# measurementBoard.net
KiCad netlist of a schematic drawn in EAGLE
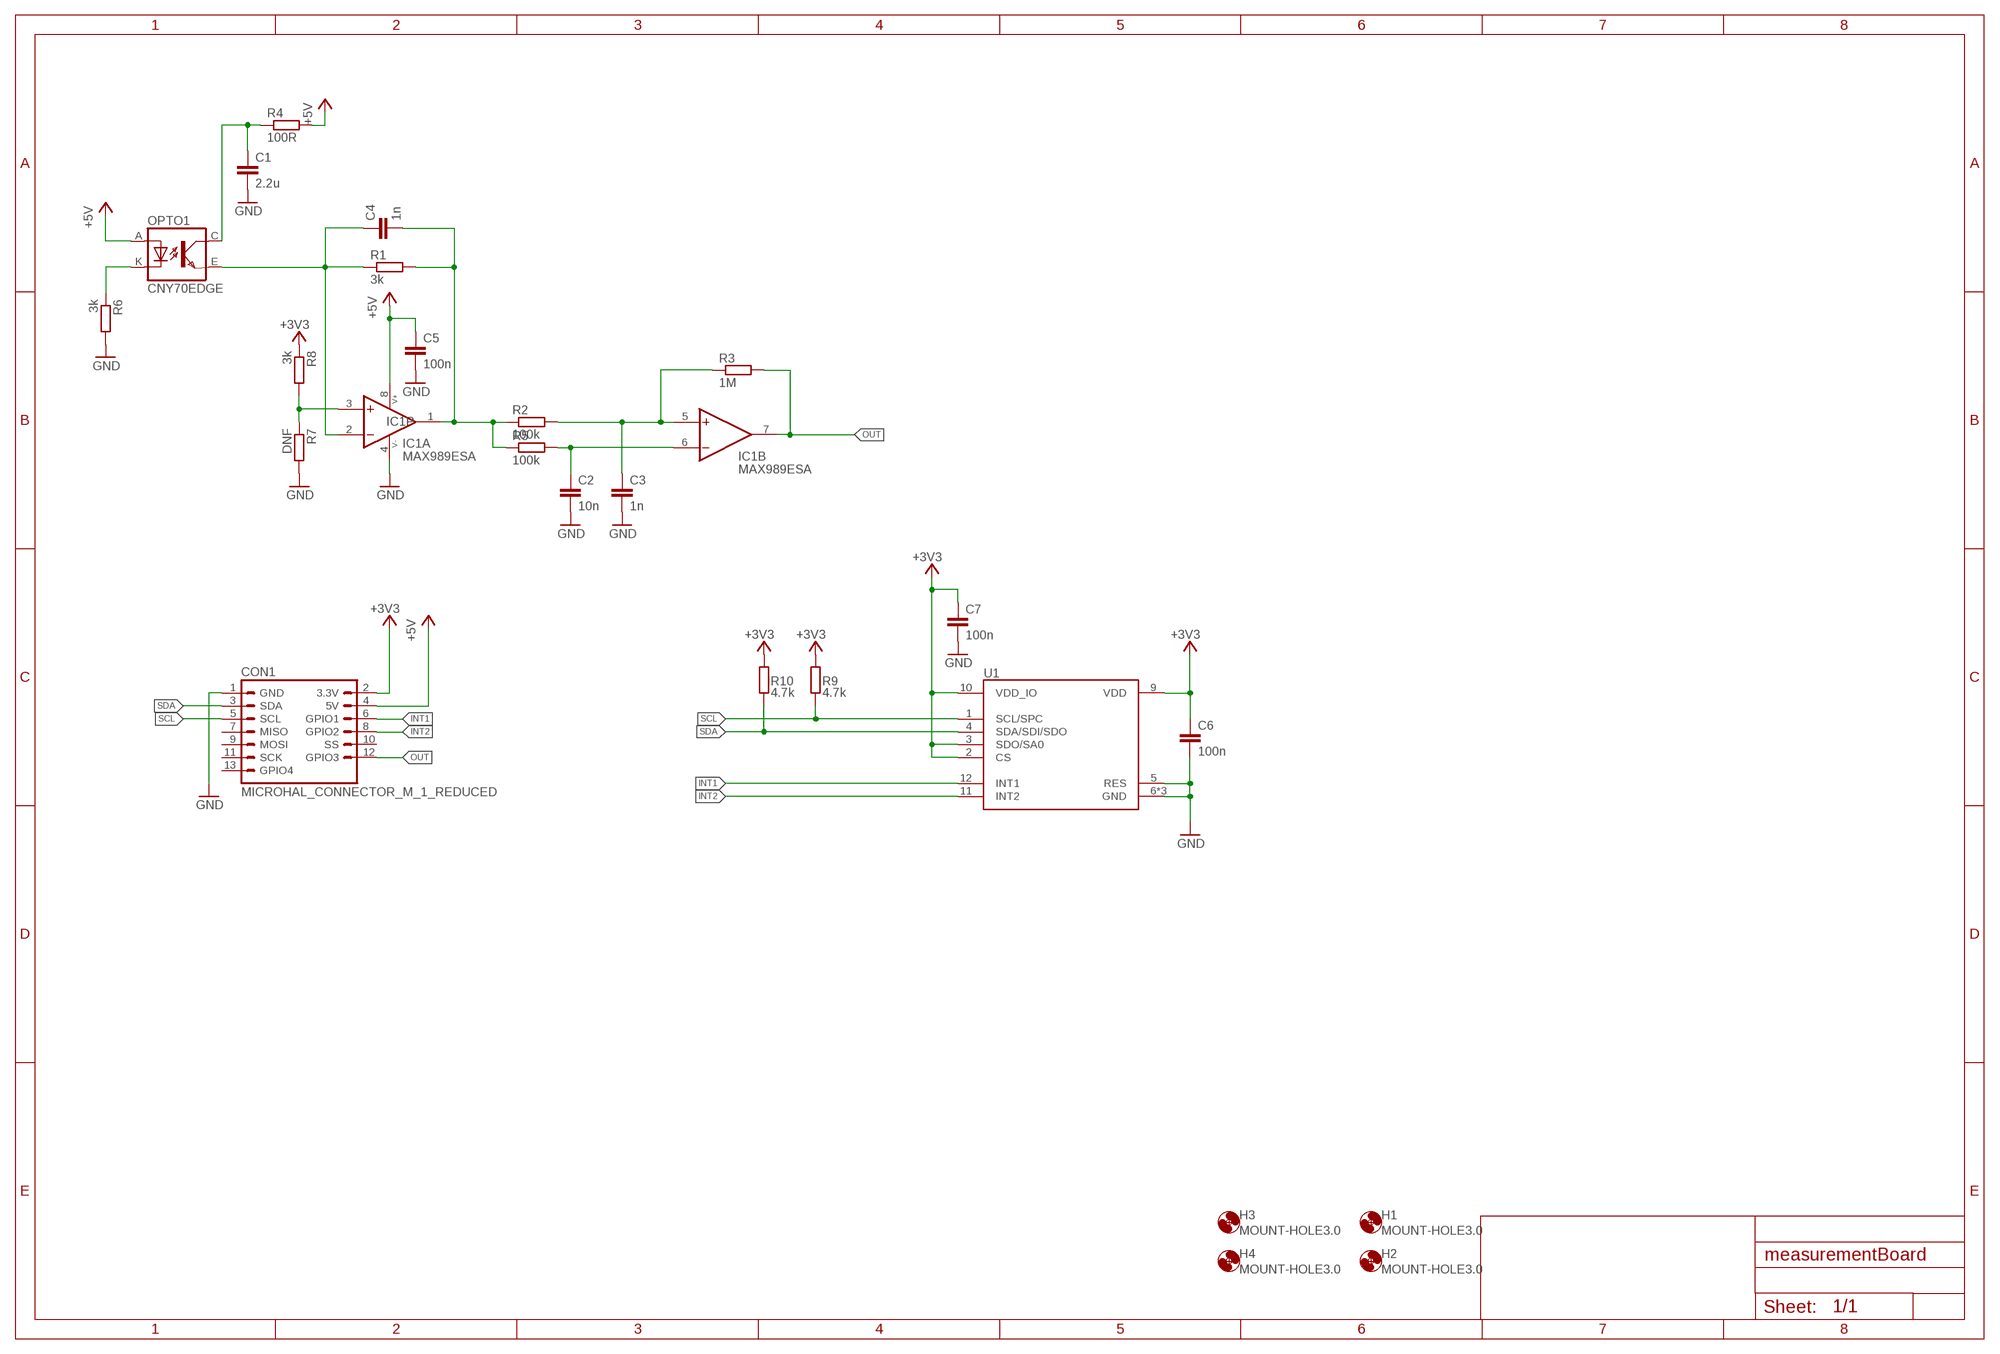
[diagram p0: schematic, sheet 1]

(export (version "E")
  (design (tool "Eeschema 10.0.6"))
  (components
    (comp (ref "C1")
      (value "2.2u")
      (footprint "eagle-import:C0603K")
      (libsource (lib "eagle-import") (part "C-EUC0603K"))
    )
    (comp (ref "C2")
      (value "10n")
      (footprint "eagle-import:C0603K")
      (libsource (lib "eagle-import") (part "C-EUC0603K"))
    )
    (comp (ref "C3")
      (value "1n")
      (footprint "eagle-import:C0603K")
      (libsource (lib "eagle-import") (part "C-EUC0603K"))
    )
    (comp (ref "C4")
      (value "1n")
      (footprint "eagle-import:C0603K")
      (libsource (lib "eagle-import") (part "C-EUC0603K"))
    )
    (comp (ref "C5")
      (value "100n")
      (footprint "eagle-import:C0603K")
      (libsource (lib "eagle-import") (part "C-EUC0603K"))
    )
    (comp (ref "C6")
      (value "100n")
      (footprint "eagle-import:C0603K")
      (libsource (lib "eagle-import") (part "C-EUC0603K"))
    )
    (comp (ref "C7")
      (value "100n")
      (footprint "eagle-import:C0603K")
      (libsource (lib "eagle-import") (part "C-EUC0603K"))
    )
    (comp (ref "CON1")
      (value "MICROHAL_CONNECTOR_M_1_REDUCED")
      (footprint "eagle-import:MICROHAL_CONNECTOR_M_1_REDUCED_EDGE")
      (libsource (lib "eagle-import") (part "MICROHAL_CONNECTOR_M_1_REDUCED"))
    )
    (comp (ref "H1")
      (value "MOUNT-HOLE3.0")
      (footprint "eagle-import:3,0")
      (libsource (lib "eagle-import") (part "MOUNT-HOLE3.0"))
    )
    (comp (ref "H2")
      (value "MOUNT-HOLE3.0")
      (footprint "eagle-import:3,0")
      (libsource (lib "eagle-import") (part "MOUNT-HOLE3.0"))
    )
    (comp (ref "H3")
      (value "MOUNT-HOLE3.0")
      (footprint "eagle-import:3,0")
      (libsource (lib "eagle-import") (part "MOUNT-HOLE3.0"))
    )
    (comp (ref "H4")
      (value "MOUNT-HOLE3.0")
      (footprint "eagle-import:3,0")
      (libsource (lib "eagle-import") (part "MOUNT-HOLE3.0"))
    )
    (comp (ref "IC1")
      (value "MAX989ESA")
      (footprint "eagle-import:SO08")
      (fields (field (name "MF") "MAXIM") (field (name "MPN") "MAX989ESA+"))
      (libsource (lib "eagle-import") (part "MAX9ESA89"))
    )
    (comp (ref "OPTO1")
      (value "CNY70EDGE")
      (footprint "eagle-import:CNY70_EDGE")
      (libsource (lib "eagle-import") (part "CNY70EDGE"))
    )
    (comp (ref "R1")
      (value "3k")
      (footprint "eagle-import:R0603")
      (libsource (lib "eagle-import") (part "R-EU_R0603"))
    )
    (comp (ref "R2")
      (value "100k")
      (footprint "eagle-import:R0603")
      (libsource (lib "eagle-import") (part "R-EU_R0603"))
    )
    (comp (ref "R3")
      (value "1M")
      (footprint "eagle-import:R0603")
      (libsource (lib "eagle-import") (part "R-EU_R0603"))
    )
    (comp (ref "R4")
      (value "100R")
      (footprint "eagle-import:R0603")
      (libsource (lib "eagle-import") (part "R-EU_R0603"))
    )
    (comp (ref "R5")
      (value "100k")
      (footprint "eagle-import:R0603")
      (libsource (lib "eagle-import") (part "R-EU_R0603"))
    )
    (comp (ref "R6")
      (value "3k")
      (footprint "eagle-import:R0603")
      (libsource (lib "eagle-import") (part "R-EU_R0603"))
    )
    (comp (ref "R7")
      (value "DNF")
      (footprint "eagle-import:R0603")
      (libsource (lib "eagle-import") (part "R-EU_R0603"))
    )
    (comp (ref "R8")
      (value "3k")
      (footprint "eagle-import:R0603")
      (libsource (lib "eagle-import") (part "R-EU_R0603"))
    )
    (comp (ref "R9")
      (value "4.7k")
      (footprint "eagle-import:R0603")
      (libsource (lib "eagle-import") (part "R-EU_R0603"))
    )
    (comp (ref "R10")
      (value "4.7k")
      (footprint "eagle-import:R0603")
      (libsource (lib "eagle-import") (part "R-EU_R0603"))
    )
    (comp (ref "U1")
      (value "LIS2DH12")
      (footprint "eagle-import:LGA-12")
      (libsource (lib "eagle-import") (part "LIS2DH12"))
    )
  )
  (nets
    (net (code "1") (name "+3V3") (class "Default")
      (node (ref "C6") (pin "1") (pinfunction "1_1") (pintype "passive"))
      (node (ref "C7") (pin "1") (pinfunction "1_1") (pintype "passive"))
      (node (ref "CON1") (pin "2") (pinfunction "3.3V_2") (pintype "passive"))
      (node (ref "R10") (pin "1") (pinfunction "1_1") (pintype "passive"))
      (node (ref "R8") (pin "1") (pinfunction "1_1") (pintype "passive"))
      (node (ref "R9") (pin "1") (pinfunction "1_1") (pintype "passive"))
      (node (ref "U1") (pin "10") (pinfunction "VDD_IO_10") (pintype "power_in"))
      (node (ref "U1") (pin "2") (pinfunction "CS_2") (pintype "bidirectional"))
      (node (ref "U1") (pin "3") (pinfunction "SDO/SA0_3") (pintype "bidirectional"))
      (node (ref "U1") (pin "9") (pinfunction "VDD_9") (pintype "power_in"))
    )
    (net (code "2") (name "+5V") (class "Default")
      (node (ref "C5") (pin "1") (pinfunction "1_1") (pintype "passive"))
      (node (ref "CON1") (pin "4") (pinfunction "5V_4") (pintype "passive"))
      (node (ref "IC1") (pin "8") (pinfunction "V+_8") (pintype "power_in"))
      (node (ref "OPTO1") (pin "A") (pinfunction "A_A") (pintype "passive"))
      (node (ref "R4") (pin "2") (pinfunction "2_2") (pintype "passive"))
    )
    (net (code "3") (name "GND") (class "Default")
      (node (ref "C1") (pin "2") (pinfunction "2_2") (pintype "passive"))
      (node (ref "C2") (pin "2") (pinfunction "2_2") (pintype "passive"))
      (node (ref "C3") (pin "2") (pinfunction "2_2") (pintype "passive"))
      (node (ref "C5") (pin "2") (pinfunction "2_2") (pintype "passive"))
      (node (ref "C6") (pin "2") (pinfunction "2_2") (pintype "passive"))
      (node (ref "C7") (pin "2") (pinfunction "2_2") (pintype "passive"))
      (node (ref "CON1") (pin "1") (pinfunction "GND_1") (pintype "passive"))
      (node (ref "IC1") (pin "4") (pinfunction "V-_4") (pintype "power_in"))
      (node (ref "R6") (pin "2") (pinfunction "2_2") (pintype "passive"))
      (node (ref "R7") (pin "2") (pinfunction "2_2") (pintype "passive"))
      (node (ref "U1") (pin "5") (pinfunction "RES_5") (pintype "power_in"))
      (node (ref "U1") (pin "6") (pinfunction "GND_6") (pintype "power_in"))
      (node (ref "U1") (pin "7") (pinfunction "GND_7") (pintype "power_in"))
      (node (ref "U1") (pin "8") (pinfunction "GND_8") (pintype "power_in"))
    )
    (net (code "4") (name "INT1") (class "Default")
      (node (ref "CON1") (pin "6") (pinfunction "GPIO1_6") (pintype "passive"))
      (node (ref "U1") (pin "12") (pinfunction "INT1_12") (pintype "output"))
    )
    (net (code "5") (name "INT2") (class "Default")
      (node (ref "CON1") (pin "8") (pinfunction "GPIO2_8") (pintype "passive"))
      (node (ref "U1") (pin "11") (pinfunction "INT2_11") (pintype "output"))
    )
    (net (code "6") (name "Net-(IC1A-+IN)") (class "Default")
      (node (ref "IC1") (pin "3") (pinfunction "+IN_3") (pintype "input"))
      (node (ref "R7") (pin "1") (pinfunction "1_1") (pintype "passive"))
      (node (ref "R8") (pin "2") (pinfunction "2_2") (pintype "passive"))
    )
    (net (code "7") (name "Net-(IC1A--IN)") (class "Default")
      (node (ref "C4") (pin "1") (pinfunction "1_1") (pintype "passive"))
      (node (ref "IC1") (pin "2") (pinfunction "-IN_2") (pintype "input"))
      (node (ref "OPTO1") (pin "E") (pinfunction "EMI_E") (pintype "passive"))
      (node (ref "R1") (pin "1") (pinfunction "1_1") (pintype "passive"))
    )
    (net (code "8") (name "Net-(IC1A-OUT)") (class "Default")
      (node (ref "C4") (pin "2") (pinfunction "2_2") (pintype "passive"))
      (node (ref "IC1") (pin "1") (pinfunction "OUT_1") (pintype "output"))
      (node (ref "R1") (pin "2") (pinfunction "2_2") (pintype "passive"))
      (node (ref "R2") (pin "1") (pinfunction "1_1") (pintype "passive"))
      (node (ref "R5") (pin "1") (pinfunction "1_1") (pintype "passive"))
    )
    (net (code "9") (name "Net-(IC1B-+IN)") (class "Default")
      (node (ref "C3") (pin "1") (pinfunction "1_1") (pintype "passive"))
      (node (ref "IC1") (pin "5") (pinfunction "+IN_5") (pintype "input"))
      (node (ref "R2") (pin "2") (pinfunction "2_2") (pintype "passive"))
      (node (ref "R3") (pin "1") (pinfunction "1_1") (pintype "passive"))
    )
    (net (code "10") (name "Net-(IC1B--IN)") (class "Default")
      (node (ref "C2") (pin "1") (pinfunction "1_1") (pintype "passive"))
      (node (ref "IC1") (pin "6") (pinfunction "-IN_6") (pintype "input"))
      (node (ref "R5") (pin "2") (pinfunction "2_2") (pintype "passive"))
    )
    (net (code "11") (name "Net-(OPTO1-C)") (class "Default")
      (node (ref "OPTO1") (pin "K") (pinfunction "C_K") (pintype "passive"))
      (node (ref "R6") (pin "1") (pinfunction "1_1") (pintype "passive"))
    )
    (net (code "12") (name "Net-(OPTO1-COL)") (class "Default")
      (node (ref "C1") (pin "1") (pinfunction "1_1") (pintype "passive"))
      (node (ref "OPTO1") (pin "C") (pinfunction "COL_C") (pintype "passive"))
      (node (ref "R4") (pin "1") (pinfunction "1_1") (pintype "passive"))
    )
    (net (code "13") (name "OUT") (class "Default")
      (node (ref "CON1") (pin "12") (pinfunction "GPIO3_12") (pintype "bidirectional"))
      (node (ref "IC1") (pin "7") (pinfunction "OUT_7") (pintype "output"))
      (node (ref "R3") (pin "2") (pinfunction "2_2") (pintype "passive"))
    )
    (net (code "14") (name "SCL") (class "Default")
      (node (ref "CON1") (pin "5") (pinfunction "SCL_5") (pintype "passive"))
      (node (ref "R9") (pin "2") (pinfunction "2_2") (pintype "passive"))
      (node (ref "U1") (pin "1") (pinfunction "SCL/SPC_1") (pintype "input"))
    )
    (net (code "15") (name "SDA") (class "Default")
      (node (ref "CON1") (pin "3") (pinfunction "SDA_3") (pintype "passive"))
      (node (ref "R10") (pin "2") (pinfunction "2_2") (pintype "passive"))
      (node (ref "U1") (pin "4") (pinfunction "SDA/SDI/SDO_4") (pintype "input"))
    )
    (net (code "16") (name "unconnected-(CON1-GPIO4-Pad13)") (class "Default")
      (node (ref "CON1") (pin "13") (pinfunction "GPIO4_13") (pintype "bidirectional"))
    )
    (net (code "17") (name "unconnected-(CON1-MISO-Pad7)") (class "Default")
      (node (ref "CON1") (pin "7") (pinfunction "MISO_7") (pintype "passive"))
    )
    (net (code "18") (name "unconnected-(CON1-MOSI-Pad9)") (class "Default")
      (node (ref "CON1") (pin "9") (pinfunction "MOSI_9") (pintype "passive"))
    )
    (net (code "19") (name "unconnected-(CON1-SCK-Pad11)") (class "Default")
      (node (ref "CON1") (pin "11") (pinfunction "SCK_11") (pintype "passive"))
    )
    (net (code "20") (name "unconnected-(CON1-SS-Pad10)") (class "Default")
      (node (ref "CON1") (pin "10") (pinfunction "SS_10") (pintype "passive"))
    )
  )
)
